# PolivoksVCF.net
KiCad netlist of a schematic drawn in EAGLE
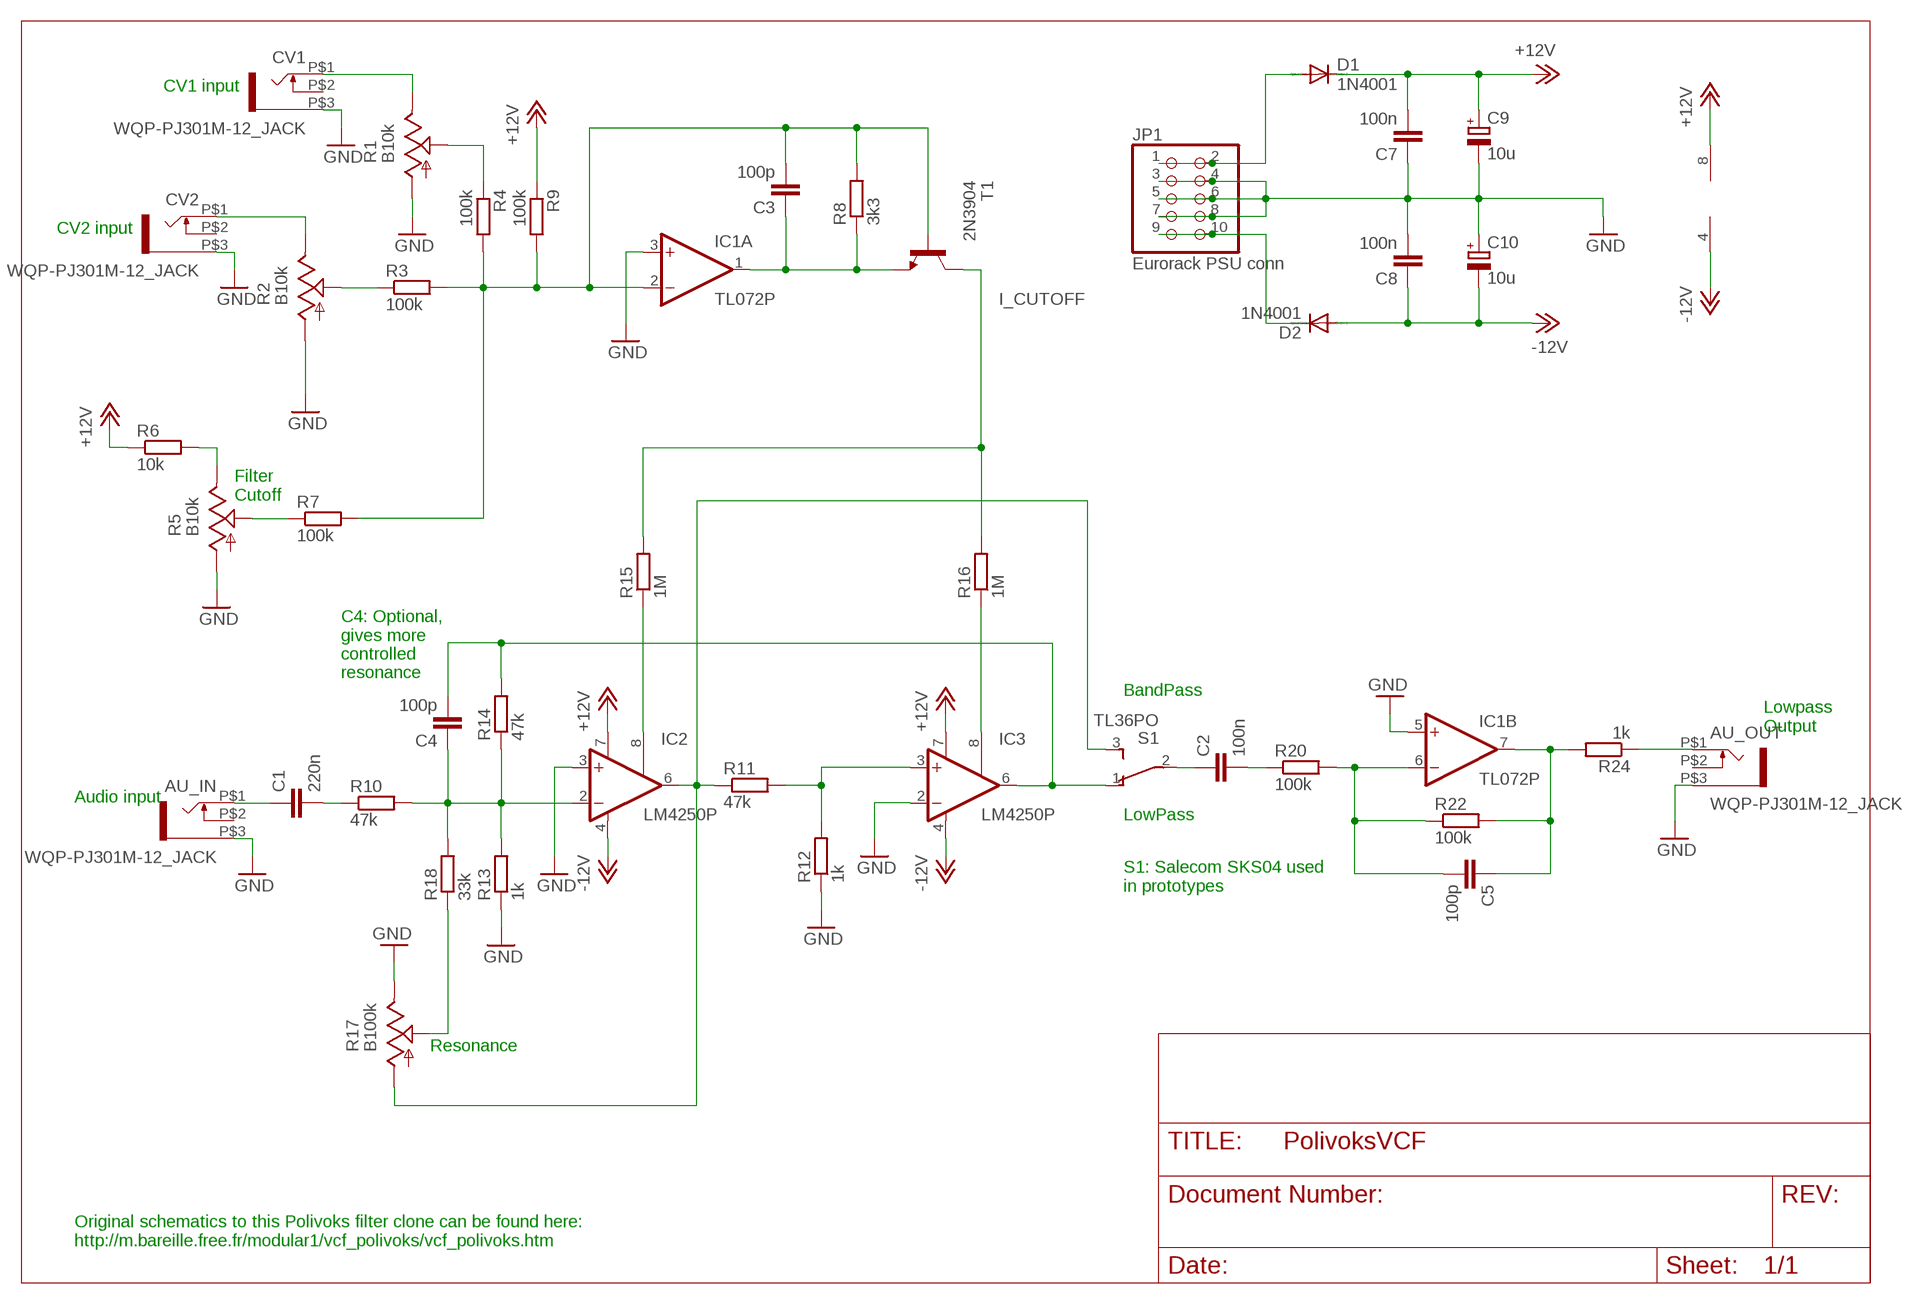
[diagram p0: schematic, sheet 1]

(export (version "E")
  (design (tool "Eeschema 10.0.6"))
  (components
    (comp (ref "AU_IN")
      (value "WQP-PJ301M-12_JACK")
      (footprint "eagle-import:WQP-PJ301M-12_JACK")
      (libsource (lib "eagle-import") (part "WQP-PJ301M-12_JACK"))
    )
    (comp (ref "AU_OUT")
      (value "WQP-PJ301M-12_JACK")
      (footprint "eagle-import:WQP-PJ301M-12_JACK")
      (libsource (lib "eagle-import") (part "WQP-PJ301M-12_JACK"))
    )
    (comp (ref "C1")
      (value "220n")
      (footprint "eagle-import:C050-045X075")
      (libsource (lib "eagle-import") (part "C-EU050-045X075"))
    )
    (comp (ref "C2")
      (value "100n")
      (footprint "eagle-import:C050-025X075")
      (libsource (lib "eagle-import") (part "C-EU050-025X075"))
    )
    (comp (ref "C3")
      (value "100p")
      (footprint "eagle-import:C025-025X050")
      (libsource (lib "eagle-import") (part "C-EU025-025X050"))
    )
    (comp (ref "C4")
      (value "100p")
      (footprint "eagle-import:C025-025X050")
      (libsource (lib "eagle-import") (part "C-EU025-025X050"))
    )
    (comp (ref "C5")
      (value "100p")
      (footprint "eagle-import:C025-025X050")
      (libsource (lib "eagle-import") (part "C-EU025-025X050"))
    )
    (comp (ref "C7")
      (value "100n")
      (footprint "eagle-import:C025-025X050")
      (libsource (lib "eagle-import") (part "C-EU025-025X050"))
    )
    (comp (ref "C8")
      (value "100n")
      (footprint "eagle-import:C025-025X050")
      (libsource (lib "eagle-import") (part "C-EU025-025X050"))
    )
    (comp (ref "C9")
      (value "10u")
      (footprint "eagle-import:E2,5-5")
      (libsource (lib "eagle-import") (part "CPOL-EUE2.5-5"))
    )
    (comp (ref "C10")
      (value "10u")
      (footprint "eagle-import:E2,5-5")
      (libsource (lib "eagle-import") (part "CPOL-EUE2.5-5"))
    )
    (comp (ref "CV1")
      (value "WQP-PJ301M-12_JACK")
      (footprint "eagle-import:WQP-PJ301M-12_JACK")
      (libsource (lib "eagle-import") (part "WQP-PJ301M-12_JACK"))
    )
    (comp (ref "CV2")
      (value "WQP-PJ301M-12_JACK")
      (footprint "eagle-import:WQP-PJ301M-12_JACK")
      (libsource (lib "eagle-import") (part "WQP-PJ301M-12_JACK"))
    )
    (comp (ref "D1")
      (value "1N4001")
      (footprint "eagle-import:D-5")
      (libsource (lib "eagle-import") (part "DIODE-D-5"))
    )
    (comp (ref "D2")
      (value "1N4001")
      (footprint "eagle-import:D-5")
      (libsource (lib "eagle-import") (part "DIODE-D-5"))
    )
    (comp (ref "IC1")
      (value "TL072P")
      (footprint "eagle-import:DIL08")
      (libsource (lib "eagle-import") (part "TL072P"))
    )
    (comp (ref "IC2")
      (value "LM4250P")
      (footprint "eagle-import:DIL08")
      (libsource (lib "eagle-import") (part "LM4250P"))
    )
    (comp (ref "IC3")
      (value "LM4250P")
      (footprint "eagle-import:DIL08")
      (libsource (lib "eagle-import") (part "LM4250P"))
    )
    (comp (ref "JP1")
      (value "Eurorack PSU conn")
      (footprint "eagle-import:2X05")
      (libsource (lib "eagle-import") (part "PINHD-2X5"))
    )
    (comp (ref "R1")
      (value "B10k")
      (footprint "eagle-import:ALPS_POT_VERTICAL")
      (libsource (lib "eagle-import") (part "POT_USVERTICAL"))
    )
    (comp (ref "R2")
      (value "B10k")
      (footprint "eagle-import:ALPS_POT_VERTICAL")
      (libsource (lib "eagle-import") (part "POT_USVERTICAL"))
    )
    (comp (ref "R3")
      (value "100k")
      (footprint "eagle-import:0207_2V")
      (libsource (lib "eagle-import") (part "R-EU_0207/2V"))
    )
    (comp (ref "R4")
      (value "100k")
      (footprint "eagle-import:0207_2V")
      (libsource (lib "eagle-import") (part "R-EU_0207/2V"))
    )
    (comp (ref "R5")
      (value "B10k")
      (footprint "eagle-import:ALPS_POT_VERTICAL")
      (libsource (lib "eagle-import") (part "POT_USVERTICAL"))
    )
    (comp (ref "R6")
      (value "10k")
      (footprint "eagle-import:0207_2V")
      (libsource (lib "eagle-import") (part "R-EU_0207/2V"))
    )
    (comp (ref "R7")
      (value "100k")
      (footprint "eagle-import:0207_2V")
      (libsource (lib "eagle-import") (part "R-EU_0207/2V"))
    )
    (comp (ref "R8")
      (value "3k3")
      (footprint "eagle-import:0207_2V")
      (libsource (lib "eagle-import") (part "R-EU_0207/2V"))
    )
    (comp (ref "R9")
      (value "100k")
      (footprint "eagle-import:0207_2V")
      (libsource (lib "eagle-import") (part "R-EU_0207/2V"))
    )
    (comp (ref "R10")
      (value "47k")
      (footprint "eagle-import:0207_2V")
      (libsource (lib "eagle-import") (part "R-EU_0207/2V"))
    )
    (comp (ref "R11")
      (value "47k")
      (footprint "eagle-import:0207_2V")
      (libsource (lib "eagle-import") (part "R-EU_0207/2V"))
    )
    (comp (ref "R12")
      (value "1k")
      (footprint "eagle-import:0207_2V")
      (libsource (lib "eagle-import") (part "R-EU_0207/2V"))
    )
    (comp (ref "R13")
      (value "1k")
      (footprint "eagle-import:0207_2V")
      (libsource (lib "eagle-import") (part "R-EU_0207/2V"))
    )
    (comp (ref "R14")
      (value "47k")
      (footprint "eagle-import:0207_2V")
      (libsource (lib "eagle-import") (part "R-EU_0207/2V"))
    )
    (comp (ref "R15")
      (value "1M")
      (footprint "eagle-import:0207_2V")
      (libsource (lib "eagle-import") (part "R-EU_0207/2V"))
    )
    (comp (ref "R16")
      (value "1M")
      (footprint "eagle-import:0207_2V")
      (libsource (lib "eagle-import") (part "R-EU_0207/2V"))
    )
    (comp (ref "R17")
      (value "B100k")
      (footprint "eagle-import:ALPS_POT_VERTICAL")
      (libsource (lib "eagle-import") (part "POT_USVERTICAL"))
    )
    (comp (ref "R18")
      (value "33k")
      (footprint "eagle-import:0207_2V")
      (libsource (lib "eagle-import") (part "R-EU_0207/2V"))
    )
    (comp (ref "R20")
      (value "100k")
      (footprint "eagle-import:0207_2V")
      (libsource (lib "eagle-import") (part "R-EU_0207/2V"))
    )
    (comp (ref "R22")
      (value "100k")
      (footprint "eagle-import:0207_2V")
      (libsource (lib "eagle-import") (part "R-EU_0207/2V"))
    )
    (comp (ref "R24")
      (value "1k")
      (footprint "eagle-import:0207_2V")
      (libsource (lib "eagle-import") (part "R-EU_0207/2V"))
    )
    (comp (ref "S1")
      (value "TL36PO")
      (footprint "eagle-import:TL3XPO")
      (libsource (lib "eagle-import") (part "TL36PO"))
    )
    (comp (ref "T1")
      (value "2N3904")
      (footprint "eagle-import:TO92-EBC")
      (libsource (lib "eagle-import") (part "-NPN-TO92-EBC2N3904"))
    )
  )
  (nets
    (net (code "1") (name "+12V") (class "Default")
      (node (ref "C7") (pin "2") (pinfunction "2_2") (pintype "passive"))
      (node (ref "C9") (pin "+") (pinfunction "+_+") (pintype "passive"))
      (node (ref "D1") (pin "C") (pinfunction "C_C") (pintype "passive"))
      (node (ref "IC1") (pin "8") (pinfunction "V+_8") (pintype "power_in"))
      (node (ref "IC2") (pin "7") (pinfunction "V+_7") (pintype "power_in"))
      (node (ref "IC3") (pin "7") (pinfunction "V+_7") (pintype "power_in"))
      (node (ref "R6") (pin "1") (pinfunction "1_1") (pintype "passive"))
      (node (ref "R9") (pin "1") (pinfunction "1_1") (pintype "passive"))
    )
    (net (code "2") (name "-12V") (class "Default")
      (node (ref "C10") (pin "-") (pinfunction "-_-") (pintype "passive"))
      (node (ref "C8") (pin "1") (pinfunction "1_1") (pintype "passive"))
      (node (ref "D2") (pin "A") (pinfunction "A_A") (pintype "passive"))
      (node (ref "IC1") (pin "4") (pinfunction "V-_4") (pintype "power_in"))
      (node (ref "IC2") (pin "4") (pinfunction "V-_4") (pintype "power_in"))
      (node (ref "IC3") (pin "4") (pinfunction "V-_4") (pintype "power_in"))
    )
    (net (code "3") (name "/I_CUTOFF") (class "Default")
      (node (ref "R15") (pin "2") (pinfunction "2_2") (pintype "passive"))
      (node (ref "R16") (pin "2") (pinfunction "2_2") (pintype "passive"))
      (node (ref "T1") (pin "C") (pinfunction "C_C") (pintype "passive"))
    )
    (net (code "4") (name "GND") (class "Default")
      (node (ref "AU_IN") (pin "P$3") (pinfunction "1_P$3") (pintype "passive"))
      (node (ref "AU_OUT") (pin "P$3") (pinfunction "1_P$3") (pintype "passive"))
      (node (ref "C10") (pin "+") (pinfunction "+_+") (pintype "passive"))
      (node (ref "C7") (pin "1") (pinfunction "1_1") (pintype "passive"))
      (node (ref "C8") (pin "2") (pinfunction "2_2") (pintype "passive"))
      (node (ref "C9") (pin "-") (pinfunction "-_-") (pintype "passive"))
      (node (ref "CV1") (pin "P$3") (pinfunction "1_P$3") (pintype "passive"))
      (node (ref "CV2") (pin "P$3") (pinfunction "1_P$3") (pintype "passive"))
      (node (ref "IC1") (pin "3") (pinfunction "+IN_3") (pintype "input"))
      (node (ref "IC1") (pin "5") (pinfunction "+IN_5") (pintype "input"))
      (node (ref "IC2") (pin "3") (pinfunction "+IN_3") (pintype "input"))
      (node (ref "IC3") (pin "2") (pinfunction "-IN_2") (pintype "input"))
      (node (ref "JP1") (pin "3") (pinfunction "3_3") (pintype "passive"))
      (node (ref "JP1") (pin "4") (pinfunction "4_4") (pintype "passive"))
      (node (ref "JP1") (pin "5") (pinfunction "5_5") (pintype "passive"))
      (node (ref "JP1") (pin "6") (pinfunction "6_6") (pintype "passive"))
      (node (ref "JP1") (pin "7") (pinfunction "7_7") (pintype "passive"))
      (node (ref "JP1") (pin "8") (pinfunction "8_8") (pintype "passive"))
      (node (ref "R1") (pin "P$3") (pinfunction "A_P$3") (pintype "passive"))
      (node (ref "R12") (pin "1") (pinfunction "1_1") (pintype "passive"))
      (node (ref "R13") (pin "1") (pinfunction "1_1") (pintype "passive"))
      (node (ref "R17") (pin "P$1") (pinfunction "E_P$1") (pintype "passive"))
      (node (ref "R2") (pin "P$3") (pinfunction "A_P$3") (pintype "passive"))
      (node (ref "R5") (pin "P$3") (pinfunction "A_P$3") (pintype "passive"))
    )
    (net (code "5") (name "Net-(AU_IN-2)") (class "Default")
      (node (ref "AU_IN") (pin "P$1") (pinfunction "2_P$1") (pintype "passive"))
      (node (ref "C1") (pin "1") (pinfunction "1_1") (pintype "passive"))
    )
    (net (code "6") (name "Net-(AU_OUT-2)") (class "Default")
      (node (ref "AU_OUT") (pin "P$1") (pinfunction "2_P$1") (pintype "passive"))
      (node (ref "R24") (pin "1") (pinfunction "1_1") (pintype "passive"))
    )
    (net (code "7") (name "Net-(C1-Pad2)") (class "Default")
      (node (ref "C1") (pin "2") (pinfunction "2_2") (pintype "passive"))
      (node (ref "R10") (pin "1") (pinfunction "1_1") (pintype "passive"))
    )
    (net (code "8") (name "Net-(C2-Pad2)") (class "Default")
      (node (ref "C2") (pin "2") (pinfunction "2_2") (pintype "passive"))
      (node (ref "R20") (pin "1") (pinfunction "1_1") (pintype "passive"))
    )
    (net (code "9") (name "Net-(CV1-2)") (class "Default")
      (node (ref "CV1") (pin "P$1") (pinfunction "2_P$1") (pintype "passive"))
      (node (ref "R1") (pin "P$1") (pinfunction "E_P$1") (pintype "passive"))
    )
    (net (code "10") (name "Net-(CV2-2)") (class "Default")
      (node (ref "CV2") (pin "P$1") (pinfunction "2_P$1") (pintype "passive"))
      (node (ref "R2") (pin "P$1") (pinfunction "E_P$1") (pintype "passive"))
    )
    (net (code "11") (name "Net-(D1-PadA)") (class "Default")
      (node (ref "D1") (pin "A") (pinfunction "A_A") (pintype "passive"))
      (node (ref "JP1") (pin "1") (pinfunction "1_1") (pintype "passive"))
      (node (ref "JP1") (pin "2") (pinfunction "2_2") (pintype "passive"))
    )
    (net (code "12") (name "Net-(D2-PadC)") (class "Default")
      (node (ref "D2") (pin "C") (pinfunction "C_C") (pintype "passive"))
      (node (ref "JP1") (pin "10") (pinfunction "10_10") (pintype "passive"))
      (node (ref "JP1") (pin "9") (pinfunction "9_9") (pintype "passive"))
    )
    (net (code "13") (name "Net-(IC1A--IN)") (class "Default")
      (node (ref "C3") (pin "2") (pinfunction "2_2") (pintype "passive"))
      (node (ref "IC1") (pin "2") (pinfunction "-IN_2") (pintype "input"))
      (node (ref "R3") (pin "2") (pinfunction "2_2") (pintype "passive"))
      (node (ref "R4") (pin "2") (pinfunction "2_2") (pintype "passive"))
      (node (ref "R7") (pin "2") (pinfunction "2_2") (pintype "passive"))
      (node (ref "R8") (pin "2") (pinfunction "2_2") (pintype "passive"))
      (node (ref "R9") (pin "2") (pinfunction "2_2") (pintype "passive"))
      (node (ref "T1") (pin "B") (pinfunction "B_B") (pintype "passive"))
    )
    (net (code "14") (name "Net-(IC1A-OUT)") (class "Default")
      (node (ref "C3") (pin "1") (pinfunction "1_1") (pintype "passive"))
      (node (ref "IC1") (pin "1") (pinfunction "OUT_1") (pintype "output"))
      (node (ref "R8") (pin "1") (pinfunction "1_1") (pintype "passive"))
      (node (ref "T1") (pin "E") (pinfunction "E_E") (pintype "passive"))
    )
    (net (code "15") (name "Net-(IC1B--IN)") (class "Default")
      (node (ref "C5") (pin "2") (pinfunction "2_2") (pintype "passive"))
      (node (ref "IC1") (pin "6") (pinfunction "-IN_6") (pintype "input"))
      (node (ref "R20") (pin "2") (pinfunction "2_2") (pintype "passive"))
      (node (ref "R22") (pin "1") (pinfunction "1_1") (pintype "passive"))
    )
    (net (code "16") (name "Net-(IC1B-OUT)") (class "Default")
      (node (ref "C5") (pin "1") (pinfunction "1_1") (pintype "passive"))
      (node (ref "IC1") (pin "7") (pinfunction "OUT_7") (pintype "output"))
      (node (ref "R22") (pin "2") (pinfunction "2_2") (pintype "passive"))
      (node (ref "R24") (pin "2") (pinfunction "2_2") (pintype "passive"))
    )
    (net (code "17") (name "Net-(IC2--IN)") (class "Default")
      (node (ref "C4") (pin "1") (pinfunction "1_1") (pintype "passive"))
      (node (ref "IC2") (pin "2") (pinfunction "-IN_2") (pintype "input"))
      (node (ref "R10") (pin "2") (pinfunction "2_2") (pintype "passive"))
      (node (ref "R13") (pin "2") (pinfunction "2_2") (pintype "passive"))
      (node (ref "R14") (pin "1") (pinfunction "1_1") (pintype "passive"))
      (node (ref "R18") (pin "2") (pinfunction "2_2") (pintype "passive"))
    )
    (net (code "18") (name "Net-(IC2-ISET)") (class "Default")
      (node (ref "IC2") (pin "8") (pinfunction "ISET_8") (pintype "passive"))
      (node (ref "R15") (pin "1") (pinfunction "1_1") (pintype "passive"))
    )
    (net (code "19") (name "Net-(IC2-OUT)") (class "Default")
      (node (ref "IC2") (pin "6") (pinfunction "OUT_6") (pintype "output"))
      (node (ref "R11") (pin "1") (pinfunction "1_1") (pintype "passive"))
      (node (ref "R17") (pin "P$3") (pinfunction "A_P$3") (pintype "passive"))
      (node (ref "S1") (pin "3") (pinfunction "S_3") (pintype "passive"))
    )
    (net (code "20") (name "Net-(IC3-+IN)") (class "Default")
      (node (ref "IC3") (pin "3") (pinfunction "+IN_3") (pintype "input"))
      (node (ref "R11") (pin "2") (pinfunction "2_2") (pintype "passive"))
      (node (ref "R12") (pin "2") (pinfunction "2_2") (pintype "passive"))
    )
    (net (code "21") (name "Net-(IC3-ISET)") (class "Default")
      (node (ref "IC3") (pin "8") (pinfunction "ISET_8") (pintype "passive"))
      (node (ref "R16") (pin "1") (pinfunction "1_1") (pintype "passive"))
    )
    (net (code "22") (name "Net-(IC3-OUT)") (class "Default")
      (node (ref "C4") (pin "2") (pinfunction "2_2") (pintype "passive"))
      (node (ref "IC3") (pin "6") (pinfunction "OUT_6") (pintype "output"))
      (node (ref "R14") (pin "2") (pinfunction "2_2") (pintype "passive"))
      (node (ref "S1") (pin "1") (pinfunction "O_1") (pintype "passive"))
    )
    (net (code "23") (name "Net-(R1-S)") (class "Default")
      (node (ref "R1") (pin "P$2") (pinfunction "S_P$2") (pintype "passive"))
      (node (ref "R4") (pin "1") (pinfunction "1_1") (pintype "passive"))
    )
    (net (code "24") (name "Net-(R2-S)") (class "Default")
      (node (ref "R2") (pin "P$2") (pinfunction "S_P$2") (pintype "passive"))
      (node (ref "R3") (pin "1") (pinfunction "1_1") (pintype "passive"))
    )
    (net (code "25") (name "Net-(R5-E)") (class "Default")
      (node (ref "R5") (pin "P$1") (pinfunction "E_P$1") (pintype "passive"))
      (node (ref "R6") (pin "2") (pinfunction "2_2") (pintype "passive"))
    )
    (net (code "26") (name "Net-(R5-S)") (class "Default")
      (node (ref "R5") (pin "P$2") (pinfunction "S_P$2") (pintype "passive"))
      (node (ref "R7") (pin "1") (pinfunction "1_1") (pintype "passive"))
    )
    (net (code "27") (name "Net-(R17-S)") (class "Default")
      (node (ref "R17") (pin "P$2") (pinfunction "S_P$2") (pintype "passive"))
      (node (ref "R18") (pin "1") (pinfunction "1_1") (pintype "passive"))
    )
    (net (code "28") (name "Net-(S1-P)") (class "Default")
      (node (ref "C2") (pin "1") (pinfunction "1_1") (pintype "passive"))
      (node (ref "S1") (pin "2") (pinfunction "P_2") (pintype "passive"))
    )
    (net (code "29") (name "unconnected-(AU_IN-3-PadP$2)") (class "Default")
      (node (ref "AU_IN") (pin "P$2") (pinfunction "3_P$2") (pintype "passive"))
    )
    (net (code "30") (name "unconnected-(AU_OUT-3-PadP$2)") (class "Default")
      (node (ref "AU_OUT") (pin "P$2") (pinfunction "3_P$2") (pintype "passive"))
    )
    (net (code "31") (name "unconnected-(CV1-3-PadP$2)") (class "Default")
      (node (ref "CV1") (pin "P$2") (pinfunction "3_P$2") (pintype "passive"))
    )
    (net (code "32") (name "unconnected-(CV2-3-PadP$2)") (class "Default")
      (node (ref "CV2") (pin "P$2") (pinfunction "3_P$2") (pintype "passive"))
    )
  )
)
